# 04_uart_i2c.net
KiCad netlist of a schematic drawn in Altium Designer
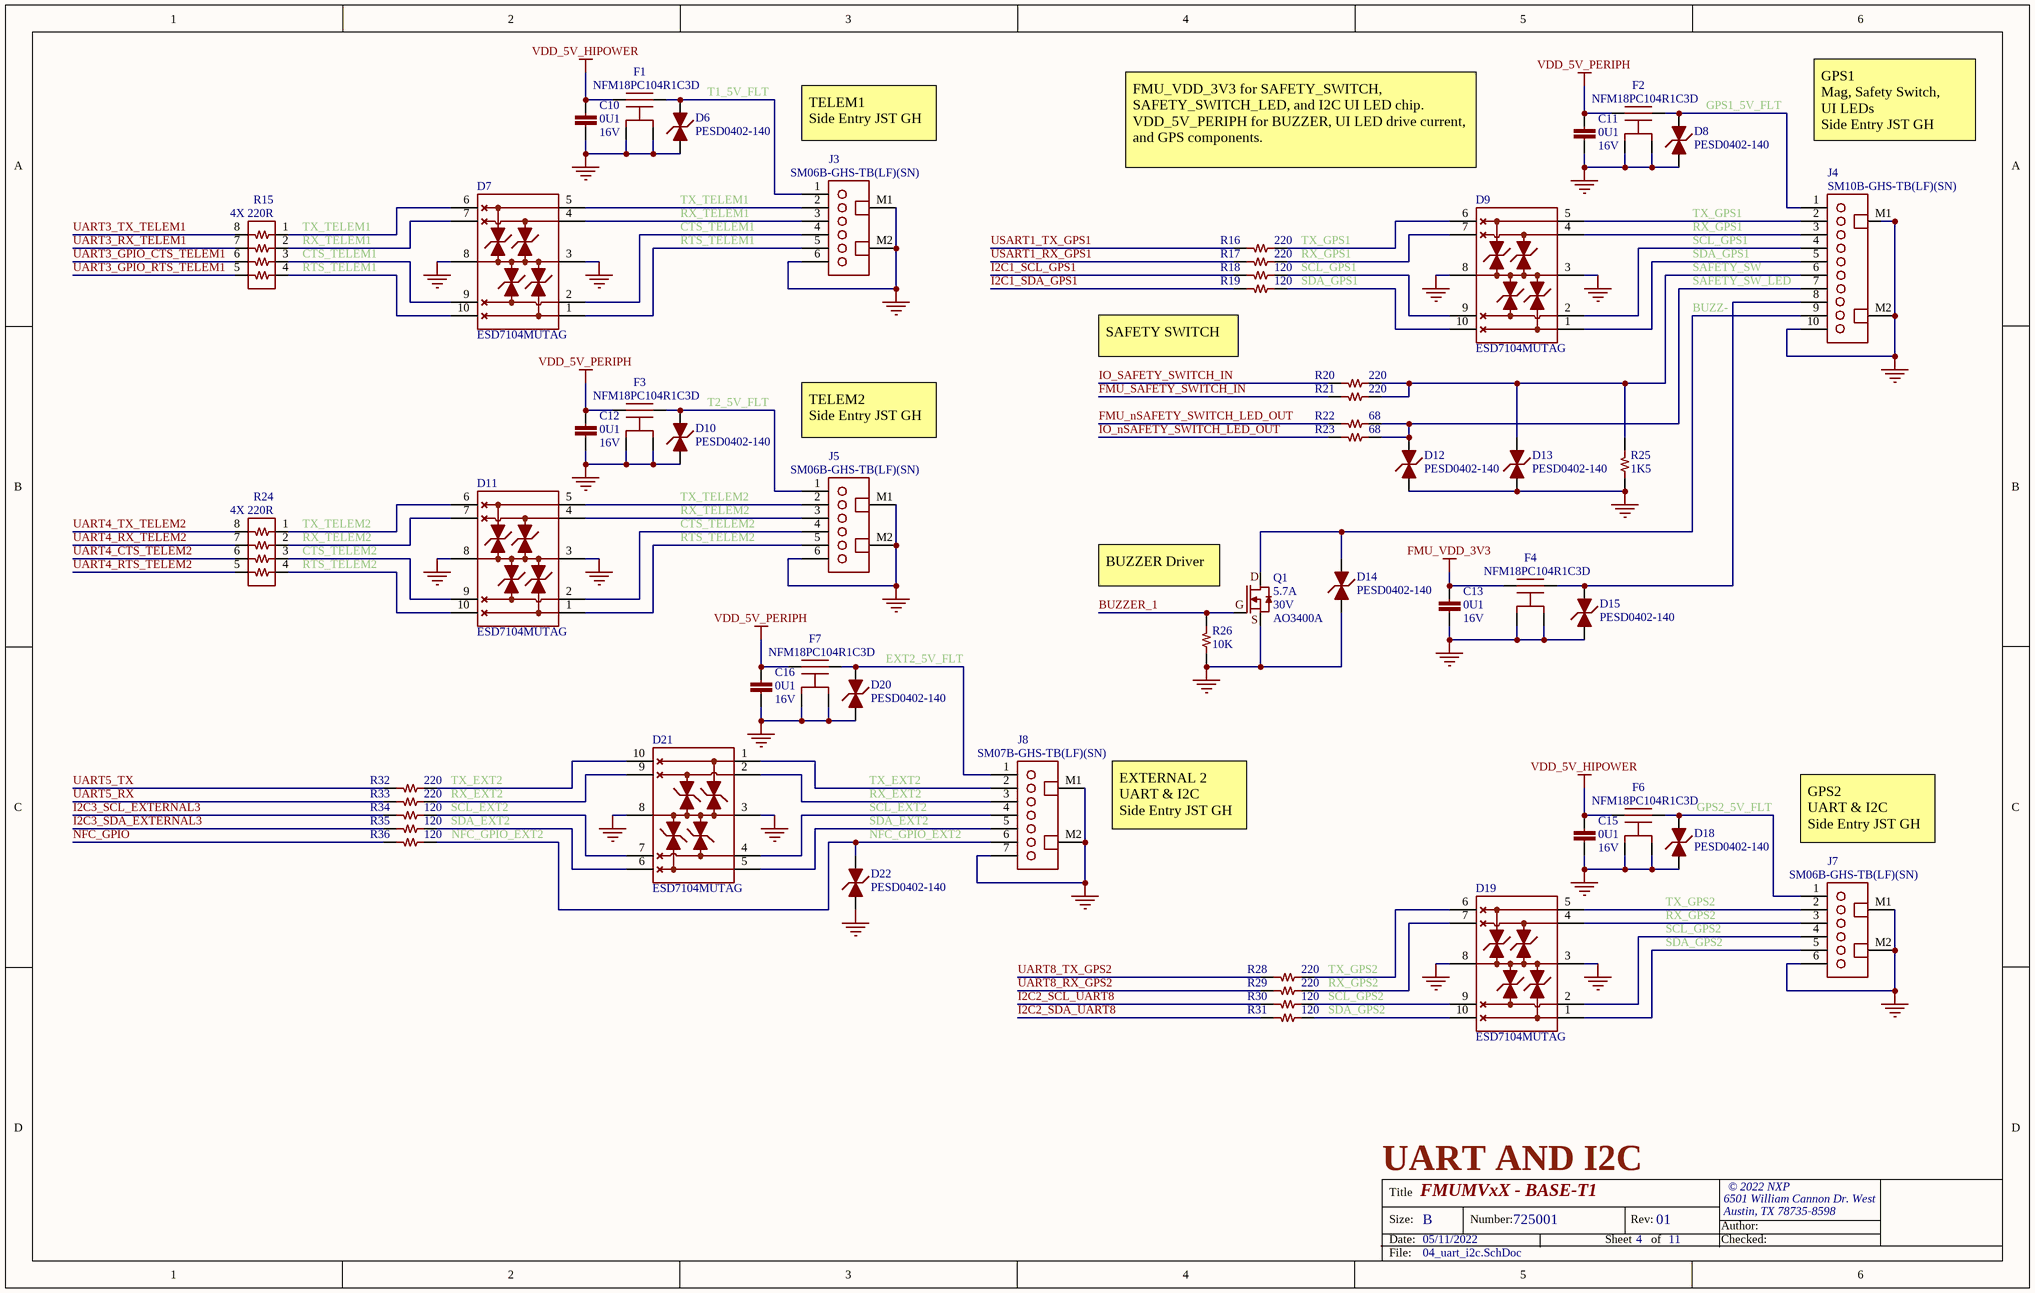
[diagram p0: 04_uart_i2c.SchDoc]

(export (version "E")
  (design (tool "Eeschema 10.0.6"))
  (components
    (comp (ref "C10")
      (value "0U1")
      (footprint "CAPC100X50X56L25N")
      (description "CAP CER 0.1UF 10% 16V X7R 0402")
      (fields
        (field (name "TOLERANCE") "±10%")
        (field (name "MANUFACTURER") "Murata Electronics")
        (field (name "VOLTAGE - RATED") "16V")
      )
      (libsource (lib "NscDG_Integrated_Library") (part "CAP_0U1_16V_X7R_0402"))
    )
    (comp (ref "C11")
      (value "0U1")
      (footprint "CAPC100X50X56L25N")
      (description "CAP CER 0.1UF 10% 16V X7R 0402")
      (fields
        (field (name "TOLERANCE") "±10%")
        (field (name "MANUFACTURER") "Murata Electronics")
        (field (name "VOLTAGE - RATED") "16V")
      )
      (libsource (lib "NscDG_Integrated_Library") (part "CAP_0U1_16V_X7R_0402"))
    )
    (comp (ref "C12")
      (value "0U1")
      (footprint "CAPC100X50X56L25N")
      (description "CAP CER 0.1UF 10% 16V X7R 0402")
      (fields
        (field (name "TOLERANCE") "±10%")
        (field (name "MANUFACTURER") "Murata Electronics")
        (field (name "VOLTAGE - RATED") "16V")
      )
      (libsource (lib "NscDG_Integrated_Library") (part "CAP_0U1_16V_X7R_0402"))
    )
    (comp (ref "C13")
      (value "0U1")
      (footprint "CAPC100X50X56L25N")
      (description "CAP CER 0.1UF 10% 16V X7R 0402")
      (fields
        (field (name "TOLERANCE") "±10%")
        (field (name "MANUFACTURER") "Murata Electronics")
        (field (name "VOLTAGE - RATED") "16V")
      )
      (libsource (lib "NscDG_Integrated_Library") (part "CAP_0U1_16V_X7R_0402"))
    )
    (comp (ref "C15")
      (value "0U1")
      (footprint "CAPC100X50X56L25N")
      (description "CAP CER 0.1UF 10% 16V X7R 0402")
      (fields
        (field (name "TOLERANCE") "±10%")
        (field (name "MANUFACTURER") "Murata Electronics")
        (field (name "VOLTAGE - RATED") "16V")
      )
      (libsource (lib "NscDG_Integrated_Library") (part "CAP_0U1_16V_X7R_0402"))
    )
    (comp (ref "C16")
      (value "0U1")
      (footprint "CAPC100X50X56L25N")
      (description "CAP CER 0.1UF 10% 16V X7R 0402")
      (fields
        (field (name "TOLERANCE") "±10%")
        (field (name "MANUFACTURER") "Murata Electronics")
        (field (name "VOLTAGE - RATED") "16V")
      )
      (libsource (lib "NscDG_Integrated_Library") (part "CAP_0U1_16V_X7R_0402"))
    )
    (comp (ref "D6")
      (value "DIODE TVS BIDIRECTIONAL 14VWM 40VC 0402")
      (footprint "DIONC100X50X43L20N")
      (fields
        (field (name "MANUFACTURER") "Littelfuse Inc.")
        (field (name "MANUFACTURER PART NUMBER") "PESD0402-140")
      )
      (libsource (lib "NscDG_Integrated_Library") (part "DIODE_TVS_0402"))
    )
    (comp (ref "D7")
      (value "DIODE TVS BIDIRECTIONAL 5V 10V 10UDFN")
      (footprint "UDFN10P50_250X100X55L35X20N")
      (fields
        (field (name "MANUFACTURER") "ON Semiconductor")
        (field (name "MANUFACTURER PART NUMBER") "ESD7104MUTAG")
      )
      (libsource (lib "NscDG_Integrated_Library") (part "DIODE_TVS_4X_10UDFN"))
    )
    (comp (ref "D8")
      (value "DIODE TVS BIDIRECTIONAL 14VWM 40VC 0402")
      (footprint "DIONC100X50X43L20N")
      (fields
        (field (name "MANUFACTURER") "Littelfuse Inc.")
        (field (name "MANUFACTURER PART NUMBER") "PESD0402-140")
      )
      (libsource (lib "NscDG_Integrated_Library") (part "DIODE_TVS_0402"))
    )
    (comp (ref "D9")
      (value "DIODE TVS BIDIRECTIONAL 5V 10V 10UDFN")
      (footprint "UDFN10P50_250X100X55L35X20N")
      (fields
        (field (name "MANUFACTURER") "ON Semiconductor")
        (field (name "MANUFACTURER PART NUMBER") "ESD7104MUTAG")
      )
      (libsource (lib "NscDG_Integrated_Library") (part "DIODE_TVS_4X_10UDFN"))
    )
    (comp (ref "D10")
      (value "DIODE TVS BIDIRECTIONAL 14VWM 40VC 0402")
      (footprint "DIONC100X50X43L20N")
      (fields
        (field (name "MANUFACTURER") "Littelfuse Inc.")
        (field (name "MANUFACTURER PART NUMBER") "PESD0402-140")
      )
      (libsource (lib "NscDG_Integrated_Library") (part "DIODE_TVS_0402"))
    )
    (comp (ref "D11")
      (value "DIODE TVS BIDIRECTIONAL 5V 10V 10UDFN")
      (footprint "UDFN10P50_250X100X55L35X20N")
      (fields
        (field (name "MANUFACTURER") "ON Semiconductor")
        (field (name "MANUFACTURER PART NUMBER") "ESD7104MUTAG")
      )
      (libsource (lib "NscDG_Integrated_Library") (part "DIODE_TVS_4X_10UDFN"))
    )
    (comp (ref "D12")
      (value "DIODE TVS BIDIRECTIONAL 14VWM 40VC 0402")
      (footprint "DIONC100X50X43L20N")
      (fields
        (field (name "MANUFACTURER") "Littelfuse Inc.")
        (field (name "MANUFACTURER PART NUMBER") "PESD0402-140")
      )
      (libsource (lib "NscDG_Integrated_Library") (part "DIODE_TVS_0402"))
    )
    (comp (ref "D13")
      (value "DIODE TVS BIDIRECTIONAL 14VWM 40VC 0402")
      (footprint "DIONC100X50X43L20N")
      (fields
        (field (name "MANUFACTURER") "Littelfuse Inc.")
        (field (name "MANUFACTURER PART NUMBER") "PESD0402-140")
      )
      (libsource (lib "NscDG_Integrated_Library") (part "DIODE_TVS_0402"))
    )
    (comp (ref "D14")
      (value "DIODE TVS BIDIRECTIONAL 14VWM 40VC 0402")
      (footprint "DIONC100X50X43L20N")
      (fields
        (field (name "MANUFACTURER") "Littelfuse Inc.")
        (field (name "MANUFACTURER PART NUMBER") "PESD0402-140")
      )
      (libsource (lib "NscDG_Integrated_Library") (part "DIODE_TVS_0402"))
    )
    (comp (ref "D15")
      (value "DIODE TVS BIDIRECTIONAL 14VWM 40VC 0402")
      (footprint "DIONC100X50X43L20N")
      (fields
        (field (name "MANUFACTURER") "Littelfuse Inc.")
        (field (name "MANUFACTURER PART NUMBER") "PESD0402-140")
      )
      (libsource (lib "NscDG_Integrated_Library") (part "DIODE_TVS_0402"))
    )
    (comp (ref "D18")
      (value "DIODE TVS BIDIRECTIONAL 14VWM 40VC 0402")
      (footprint "DIONC100X50X43L20N")
      (fields
        (field (name "MANUFACTURER") "Littelfuse Inc.")
        (field (name "MANUFACTURER PART NUMBER") "PESD0402-140")
      )
      (libsource (lib "NscDG_Integrated_Library") (part "DIODE_TVS_0402"))
    )
    (comp (ref "D19")
      (value "DIODE TVS BIDIRECTIONAL 5V 10V 10UDFN")
      (footprint "UDFN10P50_250X100X55L35X20N")
      (fields
        (field (name "MANUFACTURER") "ON Semiconductor")
        (field (name "MANUFACTURER PART NUMBER") "ESD7104MUTAG")
      )
      (libsource (lib "NscDG_Integrated_Library") (part "DIODE_TVS_4X_10UDFN"))
    )
    (comp (ref "D20")
      (value "DIODE TVS BIDIRECTIONAL 14VWM 40VC 0402")
      (footprint "DIONC100X50X43L20N")
      (fields
        (field (name "MANUFACTURER") "Littelfuse Inc.")
        (field (name "MANUFACTURER PART NUMBER") "PESD0402-140")
      )
      (libsource (lib "NscDG_Integrated_Library") (part "DIODE_TVS_0402"))
    )
    (comp (ref "D21")
      (value "DIODE TVS BIDIRECTIONAL 5V 10V 10UDFN")
      (footprint "UDFN10P50_250X100X55L35X20N")
      (fields
        (field (name "MANUFACTURER") "ON Semiconductor")
        (field (name "MANUFACTURER PART NUMBER") "ESD7104MUTAG")
      )
      (libsource (lib "NscDG_Integrated_Library") (part "DIODE_TVS_4X_10UDFN"))
    )
    (comp (ref "D22")
      (value "DIODE TVS BIDIRECTIONAL 14VWM 40VC 0402")
      (footprint "DIONC100X50X43L20N")
      (fields
        (field (name "MANUFACTURER") "Littelfuse Inc.")
        (field (name "MANUFACTURER PART NUMBER") "PESD0402-140")
      )
      (libsource (lib "NscDG_Integrated_Library") (part "DIODE_TVS_0402"))
    )
    (comp (ref "F1")
      (value "FILTER CAP FEEDTHRU 0.1UF 20% 16V 0603")
      (footprint "NFM18PC104R1C3_0603_NO_VIA")
      (fields
        (field (name "TOLERANCE") "±20%")
        (field (name "MANUFACTURER") "Murata Electronics North America")
        (field (name "MANUFACTURER PART NUMBER") "NFM18PC104R1C3D")
      )
      (libsource (lib "NscDG_Integrated_Library") (part "FILTER_0.1uF_16V_2A_NO_VIA_0603"))
    )
    (comp (ref "F2")
      (value "FILTER CAP FEEDTHRU 0.1UF 20% 16V 0603")
      (footprint "NFM18PC104R1C3_0603_NO_VIA")
      (fields
        (field (name "TOLERANCE") "±20%")
        (field (name "MANUFACTURER") "Murata Electronics North America")
        (field (name "MANUFACTURER PART NUMBER") "NFM18PC104R1C3D")
      )
      (libsource (lib "NscDG_Integrated_Library") (part "FILTER_0.1uF_16V_2A_NO_VIA_0603"))
    )
    (comp (ref "F3")
      (value "FILTER CAP FEEDTHRU 0.1UF 20% 16V 0603")
      (footprint "NFM18PC104R1C3_0603_NO_VIA")
      (fields
        (field (name "TOLERANCE") "±20%")
        (field (name "MANUFACTURER") "Murata Electronics North America")
        (field (name "MANUFACTURER PART NUMBER") "NFM18PC104R1C3D")
      )
      (libsource (lib "NscDG_Integrated_Library") (part "FILTER_0.1uF_16V_2A_NO_VIA_0603"))
    )
    (comp (ref "F4")
      (value "FILTER CAP FEEDTHRU 0.1UF 20% 16V 0603")
      (footprint "NFM18PC104R1C3_0603_NO_VIA")
      (fields
        (field (name "TOLERANCE") "±20%")
        (field (name "MANUFACTURER") "Murata Electronics North America")
        (field (name "MANUFACTURER PART NUMBER") "NFM18PC104R1C3D")
      )
      (libsource (lib "NscDG_Integrated_Library") (part "FILTER_0.1uF_16V_2A_NO_VIA_0603"))
    )
    (comp (ref "F6")
      (value "FILTER CAP FEEDTHRU 0.1UF 20% 16V 0603")
      (footprint "NFM18PC104R1C3_0603_NO_VIA")
      (fields
        (field (name "TOLERANCE") "±20%")
        (field (name "MANUFACTURER") "Murata Electronics North America")
        (field (name "MANUFACTURER PART NUMBER") "NFM18PC104R1C3D")
      )
      (libsource (lib "NscDG_Integrated_Library") (part "FILTER_0.1uF_16V_2A_NO_VIA_0603"))
    )
    (comp (ref "F7")
      (value "FILTER CAP FEEDTHRU 0.1UF 20% 16V 0603")
      (footprint "NFM18PC104R1C3_0603_NO_VIA")
      (fields
        (field (name "TOLERANCE") "±20%")
        (field (name "MANUFACTURER") "Murata Electronics North America")
        (field (name "MANUFACTURER PART NUMBER") "NFM18PC104R1C3D")
      )
      (libsource (lib "NscDG_Integrated_Library") (part "FILTER_0.1uF_16V_2A_NO_VIA_0603"))
    )
    (comp (ref "J3")
      (value "CONN HEADER GH SIDE 6POS 1.25MM SMT")
      (footprint "JST_SM06B-GHS-TBLFSN")
      (fields
        (field (name "MANUFACTURER") "JST Sales America Inc.")
        (field (name "MANUFACTURER PART NUMBER") "SM06B-GHS-TB(LF)(SN)")
      )
      (libsource (lib "NscDG_Integrated_Library") (part "CONN_JST_GH_6PIN_RA_SMT"))
    )
    (comp (ref "J4")
      (value "CONN HEADER GH 10POS SIDE 1.25MM SMT")
      (footprint "JST_SM10B-GHS-TBLFSN")
      (fields
        (field (name "MANUFACTURER") "JST Sales America Inc.")
        (field (name "MANUFACTURER PART NUMBER") "SM10B-GHS-TB(LF)(SN)")
      )
      (libsource (lib "NscDG_Integrated_Library") (part "CONN_JST_GH_10PIN_RA_SMT"))
    )
    (comp (ref "J5")
      (value "CONN HEADER GH SIDE 6POS 1.25MM SMT")
      (footprint "JST_SM06B-GHS-TBLFSN")
      (fields
        (field (name "MANUFACTURER") "JST Sales America Inc.")
        (field (name "MANUFACTURER PART NUMBER") "SM06B-GHS-TB(LF)(SN)")
      )
      (libsource (lib "NscDG_Integrated_Library") (part "CONN_JST_GH_6PIN_RA_SMT"))
    )
    (comp (ref "J7")
      (value "CONN HEADER GH SIDE 6POS 1.25MM SMT")
      (footprint "JST_SM06B-GHS-TBLFSN")
      (fields
        (field (name "MANUFACTURER") "JST Sales America Inc.")
        (field (name "MANUFACTURER PART NUMBER") "SM06B-GHS-TB(LF)(SN)")
      )
      (libsource (lib "NscDG_Integrated_Library") (part "CONN_JST_GH_6PIN_RA_SMT"))
    )
    (comp (ref "J8")
      (value "CONN HEADER GH 7POS SIDE 1.25MM SMT")
      (footprint "JST_SM07B-GHS-TBLFSN")
      (fields
        (field (name "MANUFACTURER") "JST Sales America Inc.")
        (field (name "MANUFACTURER PART NUMBER") "SM07B-GHS-TB(LF)(SN)")
      )
      (libsource (lib "NscDG_Integrated_Library") (part "CONN_JST_GH_7PIN_RA_SMT"))
    )
    (comp (ref "Q1")
      (value "TRANSISTOR MOSFET N-CH 30V 5.7A SOT23")
      (footprint "SOT23-3P95_230X110L30X43N")
      (fields
        (field (name "MANUFACTURER") "Alpha & Omega Semiconductor Inc.")
        (field (name "CURRENT") "5.7A")
        (field (name "VOLTAGE") "30V")
        (field (name "MANUFACTURER PART NUMBER") "AO3400A")
      )
      (libsource (lib "NscDG_Integrated_Library") (part "TRAN_MOSFET_N-CH_AO3400A_SMT"))
    )
    (comp (ref "R15")
      (value "4X 220R")
      (footprint "RESCAF8P80_320X160X61L30X65N")
      (description "RES ARRAY 4 RES 220 OHM 1206")
      (fields (field (name "TOLERANCE") "±5%") (field (name "MANUFACTURER") "Yageo"))
      (libsource (lib "NscDG_Integrated_Library") (part "RES_ARRAY_220_5%_1/16W_1206"))
    )
    (comp (ref "R16")
      (value "220")
      (footprint "RESC100X50X40L25")
      (description "RES SMD 220 OHM 1% 1/16W 0402")
      (fields (field (name "TOLERANCE") "±1%") (field (name "POWER") "1/16W"))
      (libsource (lib "NscDG_Integrated_Library") (part "RES_220_1%_1/16W_0402"))
    )
    (comp (ref "R17")
      (value "220")
      (footprint "RESC100X50X40L25")
      (description "RES SMD 220 OHM 1% 1/16W 0402")
      (fields (field (name "TOLERANCE") "±1%") (field (name "POWER") "1/16W"))
      (libsource (lib "NscDG_Integrated_Library") (part "RES_220_1%_1/16W_0402"))
    )
    (comp (ref "R18")
      (value "120")
      (footprint "RESC100X50X40L25")
      (description "RES SMD 120 OHM 1% 1/16W 0402")
      (fields (field (name "TOLERANCE") "±1%") (field (name "MANUFACTURER") "Yageo"))
      (libsource (lib "NscDG_Integrated_Library") (part "RES_120_1%_1/16W_0402"))
    )
    (comp (ref "R19")
      (value "120")
      (footprint "RESC100X50X40L25")
      (description "RES SMD 120 OHM 1% 1/16W 0402")
      (fields (field (name "TOLERANCE") "±1%") (field (name "MANUFACTURER") "Yageo"))
      (libsource (lib "NscDG_Integrated_Library") (part "RES_120_1%_1/16W_0402"))
    )
    (comp (ref "R20")
      (value "220")
      (footprint "RESC100X50X40L25")
      (description "RES SMD 220 OHM 1% 1/16W 0402")
      (fields (field (name "TOLERANCE") "±1%") (field (name "POWER") "1/16W"))
      (libsource (lib "NscDG_Integrated_Library") (part "RES_220_1%_1/16W_0402"))
    )
    (comp (ref "R21")
      (value "220")
      (footprint "RESC100X50X40L25")
      (description "RES SMD 220 OHM 1% 1/16W 0402")
      (fields (field (name "TOLERANCE") "±1%") (field (name "POWER") "1/16W"))
      (libsource (lib "NscDG_Integrated_Library") (part "RES_220_1%_1/16W_0402"))
    )
    (comp (ref "R22")
      (value "68")
      (footprint "RESC100X50X40L25")
      (description "RES SMD 68 OHM 1% 1/16W 0402")
      (fields (field (name "TOLERANCE") "±1%") (field (name "MANUFACTURER") "Yageo"))
      (libsource (lib "NscDG_Integrated_Library") (part "RES_68R_1%_1/16W_0402"))
    )
    (comp (ref "R23")
      (value "68")
      (footprint "RESC100X50X40L25")
      (description "RES SMD 68 OHM 1% 1/16W 0402")
      (fields (field (name "TOLERANCE") "±1%") (field (name "MANUFACTURER") "Yageo"))
      (libsource (lib "NscDG_Integrated_Library") (part "RES_68R_1%_1/16W_0402"))
    )
    (comp (ref "R24")
      (value "4X 220R")
      (footprint "RESCAF8P80_320X160X61L30X65N")
      (description "RES ARRAY 4 RES 220 OHM 1206")
      (fields (field (name "TOLERANCE") "±5%") (field (name "MANUFACTURER") "Yageo"))
      (libsource (lib "NscDG_Integrated_Library") (part "RES_ARRAY_220_5%_1/16W_1206"))
    )
    (comp (ref "R25")
      (value "1K5")
      (footprint "RESC100X50X40L25")
      (description "RES SMD 1.5K OHM 1% 1/16W 0402")
      (fields (field (name "TOLERANCE") "±1%") (field (name "MANUFACTURER") "Yageo"))
      (libsource (lib "NscDG_Integrated_Library") (part "RES_1K5_1%_1/16W_0402"))
    )
    (comp (ref "R26")
      (value "10K")
      (footprint "RESC100X50X40L25")
      (description "RES SMD 10K OHM 1% 1/16W 0402")
      (fields (field (name "TOLERANCE") "±1%") (field (name "MANUFACTURER") "Vishay Dale"))
      (libsource (lib "NscDG_Integrated_Library") (part "RES_10K_1%_1/16W_0402"))
    )
    (comp (ref "R28")
      (value "220")
      (footprint "RESC100X50X40L25")
      (description "RES SMD 220 OHM 1% 1/16W 0402")
      (fields (field (name "TOLERANCE") "±1%") (field (name "POWER") "1/16W"))
      (libsource (lib "NscDG_Integrated_Library") (part "RES_220_1%_1/16W_0402"))
    )
    (comp (ref "R29")
      (value "220")
      (footprint "RESC100X50X40L25")
      (description "RES SMD 220 OHM 1% 1/16W 0402")
      (fields (field (name "TOLERANCE") "±1%") (field (name "POWER") "1/16W"))
      (libsource (lib "NscDG_Integrated_Library") (part "RES_220_1%_1/16W_0402"))
    )
    (comp (ref "R30")
      (value "120")
      (footprint "RESC100X50X40L25")
      (description "RES SMD 120 OHM 1% 1/16W 0402")
      (fields (field (name "TOLERANCE") "±1%") (field (name "MANUFACTURER") "Yageo"))
      (libsource (lib "NscDG_Integrated_Library") (part "RES_120_1%_1/16W_0402"))
    )
    (comp (ref "R31")
      (value "120")
      (footprint "RESC100X50X40L25")
      (description "RES SMD 120 OHM 1% 1/16W 0402")
      (fields (field (name "TOLERANCE") "±1%") (field (name "MANUFACTURER") "Yageo"))
      (libsource (lib "NscDG_Integrated_Library") (part "RES_120_1%_1/16W_0402"))
    )
    (comp (ref "R32")
      (value "220")
      (footprint "RESC100X50X40L25")
      (description "RES SMD 220 OHM 1% 1/16W 0402")
      (fields (field (name "TOLERANCE") "±1%") (field (name "POWER") "1/16W"))
      (libsource (lib "NscDG_Integrated_Library") (part "RES_220_1%_1/16W_0402"))
    )
    (comp (ref "R33")
      (value "220")
      (footprint "RESC100X50X40L25")
      (description "RES SMD 220 OHM 1% 1/16W 0402")
      (fields (field (name "TOLERANCE") "±1%") (field (name "POWER") "1/16W"))
      (libsource (lib "NscDG_Integrated_Library") (part "RES_220_1%_1/16W_0402"))
    )
    (comp (ref "R34")
      (value "120")
      (footprint "RESC100X50X40L25")
      (description "RES SMD 120 OHM 1% 1/16W 0402")
      (fields (field (name "TOLERANCE") "±1%") (field (name "MANUFACTURER") "Yageo"))
      (libsource (lib "NscDG_Integrated_Library") (part "RES_120_1%_1/16W_0402"))
    )
    (comp (ref "R35")
      (value "120")
      (footprint "RESC100X50X40L25")
      (description "RES SMD 120 OHM 1% 1/16W 0402")
      (fields (field (name "TOLERANCE") "±1%") (field (name "MANUFACTURER") "Yageo"))
      (libsource (lib "NscDG_Integrated_Library") (part "RES_120_1%_1/16W_0402"))
    )
    (comp (ref "R36")
      (value "120")
      (footprint "RESC100X50X40L25")
      (description "RES SMD 120 OHM 1% 1/16W 0402")
      (fields (field (name "TOLERANCE") "±1%") (field (name "MANUFACTURER") "Yageo"))
      (libsource (lib "NscDG_Integrated_Library") (part "RES_120_1%_1/16W_0402"))
    )
  )
  (nets
    (net (code "1") (name "/BUZZ-") (class "Default")
      (node (ref "D14") (pin "2") (pinfunction "2_2") (pintype "passive"))
      (node (ref "J4") (pin "9") (pinfunction "9_9") (pintype "passive"))
      (node (ref "Q1") (pin "3") (pinfunction "D_3") (pintype "passive"))
    )
    (net (code "2") (name "/BUZZER_1") (class "Default")
      (node (ref "Q1") (pin "1") (pinfunction "G_1") (pintype "passive"))
      (node (ref "R26") (pin "1") (pinfunction "1_1") (pintype "passive"))
    )
    (net (code "3") (name "/CTS_TELEM1") (class "Default")
      (node (ref "D7") (pin "2") (pinfunction "2_2") (pintype "passive"))
      (node (ref "D7") (pin "9") (pinfunction "NC_9") (pintype "passive"))
      (node (ref "J3") (pin "4") (pinfunction "4_4") (pintype "passive"))
      (node (ref "R15") (pin "3") (pinfunction "3_3") (pintype "passive"))
    )
    (net (code "4") (name "/CTS_TELEM2") (class "Default")
      (node (ref "D11") (pin "2") (pinfunction "2_2") (pintype "passive"))
      (node (ref "D11") (pin "9") (pinfunction "NC_9") (pintype "passive"))
      (node (ref "J5") (pin "4") (pinfunction "4_4") (pintype "passive"))
      (node (ref "R24") (pin "3") (pinfunction "3_3") (pintype "passive"))
    )
    (net (code "5") (name "/EXT2_5V_FLT") (class "Default")
      (node (ref "D20") (pin "2") (pinfunction "2_2") (pintype "passive"))
      (node (ref "F7") (pin "3") (pinfunction "3_3") (pintype "passive"))
      (node (ref "J8") (pin "1") (pinfunction "1_1") (pintype "passive"))
    )
    (net (code "6") (name "/FMU_SAFETY_SWITCH_IN") (class "Default")
      (node (ref "R21") (pin "1") (pinfunction "1_1") (pintype "passive"))
    )
    (net (code "7") (name "/FMU_nSAFETY_SWITCH_LED_OUT") (class "Default")
      (node (ref "R22") (pin "1") (pinfunction "1_1") (pintype "passive"))
    )
    (net (code "8") (name "/GPS1_5V_FLT") (class "Default")
      (node (ref "D8") (pin "2") (pinfunction "2_2") (pintype "passive"))
      (node (ref "F2") (pin "3") (pinfunction "3_3") (pintype "passive"))
      (node (ref "J4") (pin "1") (pinfunction "1_1") (pintype "passive"))
    )
    (net (code "9") (name "/GPS2_5V_FLT") (class "Default")
      (node (ref "D18") (pin "2") (pinfunction "2_2") (pintype "passive"))
      (node (ref "F6") (pin "3") (pinfunction "3_3") (pintype "passive"))
      (node (ref "J7") (pin "1") (pinfunction "1_1") (pintype "passive"))
    )
    (net (code "10") (name "/I2C1_SCL_GPS1") (class "Default")
      (node (ref "R18") (pin "1") (pinfunction "1_1") (pintype "passive"))
    )
    (net (code "11") (name "/I2C1_SDA_GPS1") (class "Default")
      (node (ref "R19") (pin "1") (pinfunction "1_1") (pintype "passive"))
    )
    (net (code "12") (name "/I2C2_SCL_UART8") (class "Default")
      (node (ref "R30") (pin "1") (pinfunction "1_1") (pintype "passive"))
    )
    (net (code "13") (name "/I2C2_SDA_UART8") (class "Default")
      (node (ref "R31") (pin "1") (pinfunction "1_1") (pintype "passive"))
    )
    (net (code "14") (name "/I2C3_SCL_EXTERNAL3") (class "Default")
      (node (ref "R34") (pin "1") (pinfunction "1_1") (pintype "passive"))
    )
    (net (code "15") (name "/I2C3_SDA_EXTERNAL3") (class "Default")
      (node (ref "R35") (pin "1") (pinfunction "1_1") (pintype "passive"))
    )
    (net (code "16") (name "/IO_SAFETY_SWITCH_IN") (class "Default")
      (node (ref "R20") (pin "1") (pinfunction "1_1") (pintype "passive"))
    )
    (net (code "17") (name "/IO_nSAFETY_SWITCH_LED_OUT") (class "Default")
      (node (ref "R23") (pin "1") (pinfunction "1_1") (pintype "passive"))
    )
    (net (code "18") (name "/NFC_GPIO") (class "Default")
      (node (ref "R36") (pin "1") (pinfunction "1_1") (pintype "passive"))
    )
    (net (code "19") (name "/NFC_GPIO_EXT2") (class "Default")
      (node (ref "D22") (pin "2") (pinfunction "2_2") (pintype "passive"))
      (node (ref "J8") (pin "6") (pinfunction "6_6") (pintype "passive"))
      (node (ref "R36") (pin "2") (pinfunction "2_2") (pintype "passive"))
    )
    (net (code "20") (name "/RTS_TELEM1") (class "Default")
      (node (ref "D7") (pin "1") (pinfunction "1_1") (pintype "passive"))
      (node (ref "D7") (pin "10") (pinfunction "NC_10") (pintype "passive"))
      (node (ref "J3") (pin "5") (pinfunction "5_5") (pintype "passive"))
      (node (ref "R15") (pin "4") (pinfunction "4_4") (pintype "passive"))
    )
    (net (code "21") (name "/RTS_TELEM2") (class "Default")
      (node (ref "D11") (pin "1") (pinfunction "1_1") (pintype "passive"))
      (node (ref "D11") (pin "10") (pinfunction "NC_10") (pintype "passive"))
      (node (ref "J5") (pin "5") (pinfunction "5_5") (pintype "passive"))
      (node (ref "R24") (pin "4") (pinfunction "4_4") (pintype "passive"))
    )
    (net (code "22") (name "/RX_EXT2") (class "Default")
      (node (ref "D21") (pin "2") (pinfunction "2_2") (pintype "passive"))
      (node (ref "D21") (pin "9") (pinfunction "NC_9") (pintype "passive"))
      (node (ref "J8") (pin "3") (pinfunction "3_3") (pintype "passive"))
      (node (ref "R33") (pin "2") (pinfunction "2_2") (pintype "passive"))
    )
    (net (code "23") (name "/RX_GPS1") (class "Default")
      (node (ref "D9") (pin "4") (pinfunction "4_4") (pintype "passive"))
      (node (ref "D9") (pin "7") (pinfunction "NC_7") (pintype "passive"))
      (node (ref "J4") (pin "3") (pinfunction "3_3") (pintype "passive"))
      (node (ref "R17") (pin "2") (pinfunction "2_2") (pintype "passive"))
    )
    (net (code "24") (name "/RX_GPS2") (class "Default")
      (node (ref "D19") (pin "4") (pinfunction "4_4") (pintype "passive"))
      (node (ref "D19") (pin "7") (pinfunction "NC_7") (pintype "passive"))
      (node (ref "J7") (pin "3") (pinfunction "3_3") (pintype "passive"))
      (node (ref "R29") (pin "2") (pinfunction "2_2") (pintype "passive"))
    )
    (net (code "25") (name "/RX_TELEM1") (class "Default")
      (node (ref "D7") (pin "4") (pinfunction "4_4") (pintype "passive"))
      (node (ref "D7") (pin "7") (pinfunction "NC_7") (pintype "passive"))
      (node (ref "J3") (pin "3") (pinfunction "3_3") (pintype "passive"))
      (node (ref "R15") (pin "2") (pinfunction "2_2") (pintype "passive"))
    )
    (net (code "26") (name "/RX_TELEM2") (class "Default")
      (node (ref "D11") (pin "4") (pinfunction "4_4") (pintype "passive"))
      (node (ref "D11") (pin "7") (pinfunction "NC_7") (pintype "passive"))
      (node (ref "J5") (pin "3") (pinfunction "3_3") (pintype "passive"))
      (node (ref "R24") (pin "2") (pinfunction "2_2") (pintype "passive"))
    )
    (net (code "27") (name "/SAFETY_SW") (class "Default")
      (node (ref "D13") (pin "2") (pinfunction "2_2") (pintype "passive"))
      (node (ref "J4") (pin "6") (pinfunction "6_6") (pintype "passive"))
      (node (ref "R20") (pin "2") (pinfunction "2_2") (pintype "passive"))
      (node (ref "R21") (pin "2") (pinfunction "2_2") (pintype "passive"))
      (node (ref "R25") (pin "1") (pinfunction "1_1") (pintype "passive"))
    )
    (net (code "28") (name "/SAFETY_SW_LED") (class "Default")
      (node (ref "D12") (pin "2") (pinfunction "2_2") (pintype "passive"))
      (node (ref "J4") (pin "7") (pinfunction "7_7") (pintype "passive"))
      (node (ref "R22") (pin "2") (pinfunction "2_2") (pintype "passive"))
      (node (ref "R23") (pin "2") (pinfunction "2_2") (pintype "passive"))
    )
    (net (code "29") (name "/SCL_EXT2") (class "Default")
      (node (ref "D21") (pin "4") (pinfunction "4_4") (pintype "passive"))
      (node (ref "D21") (pin "7") (pinfunction "NC_7") (pintype "passive"))
      (node (ref "J8") (pin "4") (pinfunction "4_4") (pintype "passive"))
      (node (ref "R34") (pin "2") (pinfunction "2_2") (pintype "passive"))
    )
    (net (code "30") (name "/SCL_GPS1") (class "Default")
      (node (ref "D9") (pin "2") (pinfunction "2_2") (pintype "passive"))
      (node (ref "D9") (pin "9") (pinfunction "NC_9") (pintype "passive"))
      (node (ref "J4") (pin "4") (pinfunction "4_4") (pintype "passive"))
      (node (ref "R18") (pin "2") (pinfunction "2_2") (pintype "passive"))
    )
    (net (code "31") (name "/SCL_GPS2") (class "Default")
      (node (ref "D19") (pin "2") (pinfunction "2_2") (pintype "passive"))
      (node (ref "D19") (pin "9") (pinfunction "NC_9") (pintype "passive"))
      (node (ref "J7") (pin "4") (pinfunction "4_4") (pintype "passive"))
      (node (ref "R30") (pin "2") (pinfunction "2_2") (pintype "passive"))
    )
    (net (code "32") (name "/SDA_EXT2") (class "Default")
      (node (ref "D21") (pin "5") (pinfunction "5_5") (pintype "passive"))
      (node (ref "D21") (pin "6") (pinfunction "NC_6") (pintype "passive"))
      (node (ref "J8") (pin "5") (pinfunction "5_5") (pintype "passive"))
      (node (ref "R35") (pin "2") (pinfunction "2_2") (pintype "passive"))
    )
    (net (code "33") (name "/SDA_GPS1") (class "Default")
      (node (ref "D9") (pin "1") (pinfunction "1_1") (pintype "passive"))
      (node (ref "D9") (pin "10") (pinfunction "NC_10") (pintype "passive"))
      (node (ref "J4") (pin "5") (pinfunction "5_5") (pintype "passive"))
      (node (ref "R19") (pin "2") (pinfunction "2_2") (pintype "passive"))
    )
    (net (code "34") (name "/SDA_GPS2") (class "Default")
      (node (ref "D19") (pin "1") (pinfunction "1_1") (pintype "passive"))
      (node (ref "D19") (pin "10") (pinfunction "NC_10") (pintype "passive"))
      (node (ref "J7") (pin "5") (pinfunction "5_5") (pintype "passive"))
      (node (ref "R31") (pin "2") (pinfunction "2_2") (pintype "passive"))
    )
    (net (code "35") (name "/T1_5V_FLT") (class "Default")
      (node (ref "D6") (pin "2") (pinfunction "2_2") (pintype "passive"))
      (node (ref "F1") (pin "3") (pinfunction "3_3") (pintype "passive"))
      (node (ref "J3") (pin "1") (pinfunction "1_1") (pintype "passive"))
    )
    (net (code "36") (name "/T2_5V_FLT") (class "Default")
      (node (ref "D10") (pin "2") (pinfunction "2_2") (pintype "passive"))
      (node (ref "F3") (pin "3") (pinfunction "3_3") (pintype "passive"))
      (node (ref "J5") (pin "1") (pinfunction "1_1") (pintype "passive"))
    )
    (net (code "37") (name "/TX_EXT2") (class "Default")
      (node (ref "D21") (pin "1") (pinfunction "1_1") (pintype "passive"))
      (node (ref "D21") (pin "10") (pinfunction "NC_10") (pintype "passive"))
      (node (ref "J8") (pin "2") (pinfunction "2_2") (pintype "passive"))
      (node (ref "R32") (pin "2") (pinfunction "2_2") (pintype "passive"))
    )
    (net (code "38") (name "/TX_GPS1") (class "Default")
      (node (ref "D9") (pin "5") (pinfunction "5_5") (pintype "passive"))
      (node (ref "D9") (pin "6") (pinfunction "NC_6") (pintype "passive"))
      (node (ref "J4") (pin "2") (pinfunction "2_2") (pintype "passive"))
      (node (ref "R16") (pin "2") (pinfunction "2_2") (pintype "passive"))
    )
    (net (code "39") (name "/TX_GPS2") (class "Default")
      (node (ref "D19") (pin "5") (pinfunction "5_5") (pintype "passive"))
      (node (ref "D19") (pin "6") (pinfunction "NC_6") (pintype "passive"))
      (node (ref "J7") (pin "2") (pinfunction "2_2") (pintype "passive"))
      (node (ref "R28") (pin "2") (pinfunction "2_2") (pintype "passive"))
    )
    (net (code "40") (name "/TX_TELEM1") (class "Default")
      (node (ref "D7") (pin "5") (pinfunction "5_5") (pintype "passive"))
      (node (ref "D7") (pin "6") (pinfunction "NC_6") (pintype "passive"))
      (node (ref "J3") (pin "2") (pinfunction "2_2") (pintype "passive"))
      (node (ref "R15") (pin "1") (pinfunction "1_1") (pintype "passive"))
    )
    (net (code "41") (name "/TX_TELEM2") (class "Default")
      (node (ref "D11") (pin "5") (pinfunction "5_5") (pintype "passive"))
      (node (ref "D11") (pin "6") (pinfunction "NC_6") (pintype "passive"))
      (node (ref "J5") (pin "2") (pinfunction "2_2") (pintype "passive"))
      (node (ref "R24") (pin "1") (pinfunction "1_1") (pintype "passive"))
    )
    (net (code "42") (name "/UART3_GPIO_CTS_TELEM1") (class "Default")
      (node (ref "R15") (pin "6") (pinfunction "6_6") (pintype "passive"))
    )
    (net (code "43") (name "/UART3_GPIO_RTS_TELEM1") (class "Default")
      (node (ref "R15") (pin "5") (pinfunction "5_5") (pintype "passive"))
    )
    (net (code "44") (name "/UART3_RX_TELEM1") (class "Default")
      (node (ref "R15") (pin "7") (pinfunction "7_7") (pintype "passive"))
    )
    (net (code "45") (name "/UART3_TX_TELEM1") (class "Default")
      (node (ref "R15") (pin "8") (pinfunction "8_8") (pintype "passive"))
    )
    (net (code "46") (name "/UART4_CTS_TELEM2") (class "Default")
      (node (ref "R24") (pin "6") (pinfunction "6_6") (pintype "passive"))
    )
    (net (code "47") (name "/UART4_RTS_TELEM2") (class "Default")
      (node (ref "R24") (pin "5") (pinfunction "5_5") (pintype "passive"))
    )
    (net (code "48") (name "/UART4_RX_TELEM2") (class "Default")
      (node (ref "R24") (pin "7") (pinfunction "7_7") (pintype "passive"))
    )
    (net (code "49") (name "/UART4_TX_TELEM2") (class "Default")
      (node (ref "R24") (pin "8") (pinfunction "8_8") (pintype "passive"))
    )
    (net (code "50") (name "/UART5_RX") (class "Default")
      (node (ref "R33") (pin "1") (pinfunction "1_1") (pintype "passive"))
    )
    (net (code "51") (name "/UART5_TX") (class "Default")
      (node (ref "R32") (pin "1") (pinfunction "1_1") (pintype "passive"))
    )
    (net (code "52") (name "/UART8_RX_GPS2") (class "Default")
      (node (ref "R29") (pin "1") (pinfunction "1_1") (pintype "passive"))
    )
    (net (code "53") (name "/UART8_TX_GPS2") (class "Default")
      (node (ref "R28") (pin "1") (pinfunction "1_1") (pintype "passive"))
    )
    (net (code "54") (name "/USART1_RX_GPS1") (class "Default")
      (node (ref "R17") (pin "1") (pinfunction "1_1") (pintype "passive"))
    )
    (net (code "55") (name "/USART1_TX_GPS1") (class "Default")
      (node (ref "R16") (pin "1") (pinfunction "1_1") (pintype "passive"))
    )
    (net (code "56") (name "FMU_VDD_3V3") (class "Default")
      (node (ref "C13") (pin "1") (pinfunction "1_1") (pintype "passive"))
      (node (ref "F4") (pin "1") (pinfunction "1_1") (pintype "passive"))
    )
    (net (code "57") (name "GND") (class "Default")
      (node (ref "C10") (pin "2") (pinfunction "2_2") (pintype "passive"))
      (node (ref "C11") (pin "2") (pinfunction "2_2") (pintype "passive"))
      (node (ref "C12") (pin "2") (pinfunction "2_2") (pintype "passive"))
      (node (ref "C13") (pin "2") (pinfunction "2_2") (pintype "passive"))
      (node (ref "C15") (pin "2") (pinfunction "2_2") (pintype "passive"))
      (node (ref "C16") (pin "2") (pinfunction "2_2") (pintype "passive"))
      (node (ref "D10") (pin "1") (pinfunction "1_1") (pintype "passive"))
      (node (ref "D11") (pin "3") (pinfunction "GND_3") (pintype "passive"))
      (node (ref "D11") (pin "8") (pinfunction "GND_8") (pintype "passive"))
      (node (ref "D12") (pin "1") (pinfunction "1_1") (pintype "passive"))
      (node (ref "D13") (pin "1") (pinfunction "1_1") (pintype "passive"))
      (node (ref "D14") (pin "1") (pinfunction "1_1") (pintype "passive"))
      (node (ref "D15") (pin "1") (pinfunction "1_1") (pintype "passive"))
      (node (ref "D18") (pin "1") (pinfunction "1_1") (pintype "passive"))
      (node (ref "D19") (pin "3") (pinfunction "GND_3") (pintype "passive"))
      (node (ref "D19") (pin "8") (pinfunction "GND_8") (pintype "passive"))
      (node (ref "D20") (pin "1") (pinfunction "1_1") (pintype "passive"))
      (node (ref "D21") (pin "3") (pinfunction "GND_3") (pintype "passive"))
      (node (ref "D21") (pin "8") (pinfunction "GND_8") (pintype "passive"))
      (node (ref "D22") (pin "1") (pinfunction "1_1") (pintype "passive"))
      (node (ref "D6") (pin "1") (pinfunction "1_1") (pintype "passive"))
      (node (ref "D7") (pin "3") (pinfunction "GND_3") (pintype "passive"))
      (node (ref "D7") (pin "8") (pinfunction "GND_8") (pintype "passive"))
      (node (ref "D8") (pin "1") (pinfunction "1_1") (pintype "passive"))
      (node (ref "D9") (pin "3") (pinfunction "GND_3") (pintype "passive"))
      (node (ref "D9") (pin "8") (pinfunction "GND_8") (pintype "passive"))
      (node (ref "F1") (pin "2A") (pinfunction "GND_2A") (pintype "passive"))
      (node (ref "F1") (pin "2B") (pinfunction "GND_2B") (pintype "passive"))
      (node (ref "F2") (pin "2A") (pinfunction "GND_2A") (pintype "passive"))
      (node (ref "F2") (pin "2B") (pinfunction "GND_2B") (pintype "passive"))
      (node (ref "F3") (pin "2A") (pinfunction "GND_2A") (pintype "passive"))
      (node (ref "F3") (pin "2B") (pinfunction "GND_2B") (pintype "passive"))
      (node (ref "F4") (pin "2A") (pinfunction "GND_2A") (pintype "passive"))
      (node (ref "F4") (pin "2B") (pinfunction "GND_2B") (pintype "passive"))
      (node (ref "F6") (pin "2A") (pinfunction "GND_2A") (pintype "passive"))
      (node (ref "F6") (pin "2B") (pinfunction "GND_2B") (pintype "passive"))
      (node (ref "F7") (pin "2A") (pinfunction "GND_2A") (pintype "passive"))
      (node (ref "F7") (pin "2B") (pinfunction "GND_2B") (pintype "passive"))
      (node (ref "J3") (pin "6") (pinfunction "6_6") (pintype "passive"))
      (node (ref "J3") (pin "M1") (pinfunction "M1_M1") (pintype "passive"))
      (node (ref "J3") (pin "M2") (pinfunction "M2_M2") (pintype "passive"))
      (node (ref "J4") (pin "10") (pinfunction "10_10") (pintype "passive"))
      (node (ref "J4") (pin "M1") (pinfunction "M1_M1") (pintype "passive"))
      (node (ref "J4") (pin "M2") (pinfunction "M2_M2") (pintype "passive"))
      (node (ref "J5") (pin "6") (pinfunction "6_6") (pintype "passive"))
      (node (ref "J5") (pin "M1") (pinfunction "M1_M1") (pintype "passive"))
      (node (ref "J5") (pin "M2") (pinfunction "M2_M2") (pintype "passive"))
      (node (ref "J7") (pin "6") (pinfunction "6_6") (pintype "passive"))
      (node (ref "J7") (pin "M1") (pinfunction "M1_M1") (pintype "passive"))
      (node (ref "J7") (pin "M2") (pinfunction "M2_M2") (pintype "passive"))
      (node (ref "J8") (pin "7") (pinfunction "7_7") (pintype "passive"))
      (node (ref "J8") (pin "M1") (pinfunction "M1_M1") (pintype "passive"))
      (node (ref "J8") (pin "M2") (pinfunction "M2_M2") (pintype "passive"))
      (node (ref "Q1") (pin "2") (pinfunction "S_2") (pintype "passive"))
      (node (ref "R25") (pin "2") (pinfunction "2_2") (pintype "passive"))
      (node (ref "R26") (pin "2") (pinfunction "2_2") (pintype "passive"))
    )
    (net (code "58") (name "Net-(D15-Pad2)") (class "Default")
      (node (ref "D15") (pin "2") (pinfunction "2_2") (pintype "passive"))
      (node (ref "F4") (pin "3") (pinfunction "3_3") (pintype "passive"))
      (node (ref "J4") (pin "8") (pinfunction "8_8") (pintype "passive"))
    )
    (net (code "59") (name "VDD_5V_HIPOWER") (class "Default")
      (node (ref "C10") (pin "1") (pinfunction "1_1") (pintype "passive"))
      (node (ref "C15") (pin "1") (pinfunction "1_1") (pintype "passive"))
      (node (ref "F1") (pin "1") (pinfunction "1_1") (pintype "passive"))
      (node (ref "F6") (pin "1") (pinfunction "1_1") (pintype "passive"))
    )
    (net (code "60") (name "VDD_5V_PERIPH") (class "Default")
      (node (ref "C11") (pin "1") (pinfunction "1_1") (pintype "passive"))
      (node (ref "C12") (pin "1") (pinfunction "1_1") (pintype "passive"))
      (node (ref "C16") (pin "1") (pinfunction "1_1") (pintype "passive"))
      (node (ref "F2") (pin "1") (pinfunction "1_1") (pintype "passive"))
      (node (ref "F3") (pin "1") (pinfunction "1_1") (pintype "passive"))
      (node (ref "F7") (pin "1") (pinfunction "1_1") (pintype "passive"))
    )
  )
)
